# Project_2.net
KiCad netlist of a schematic drawn in EAGLE
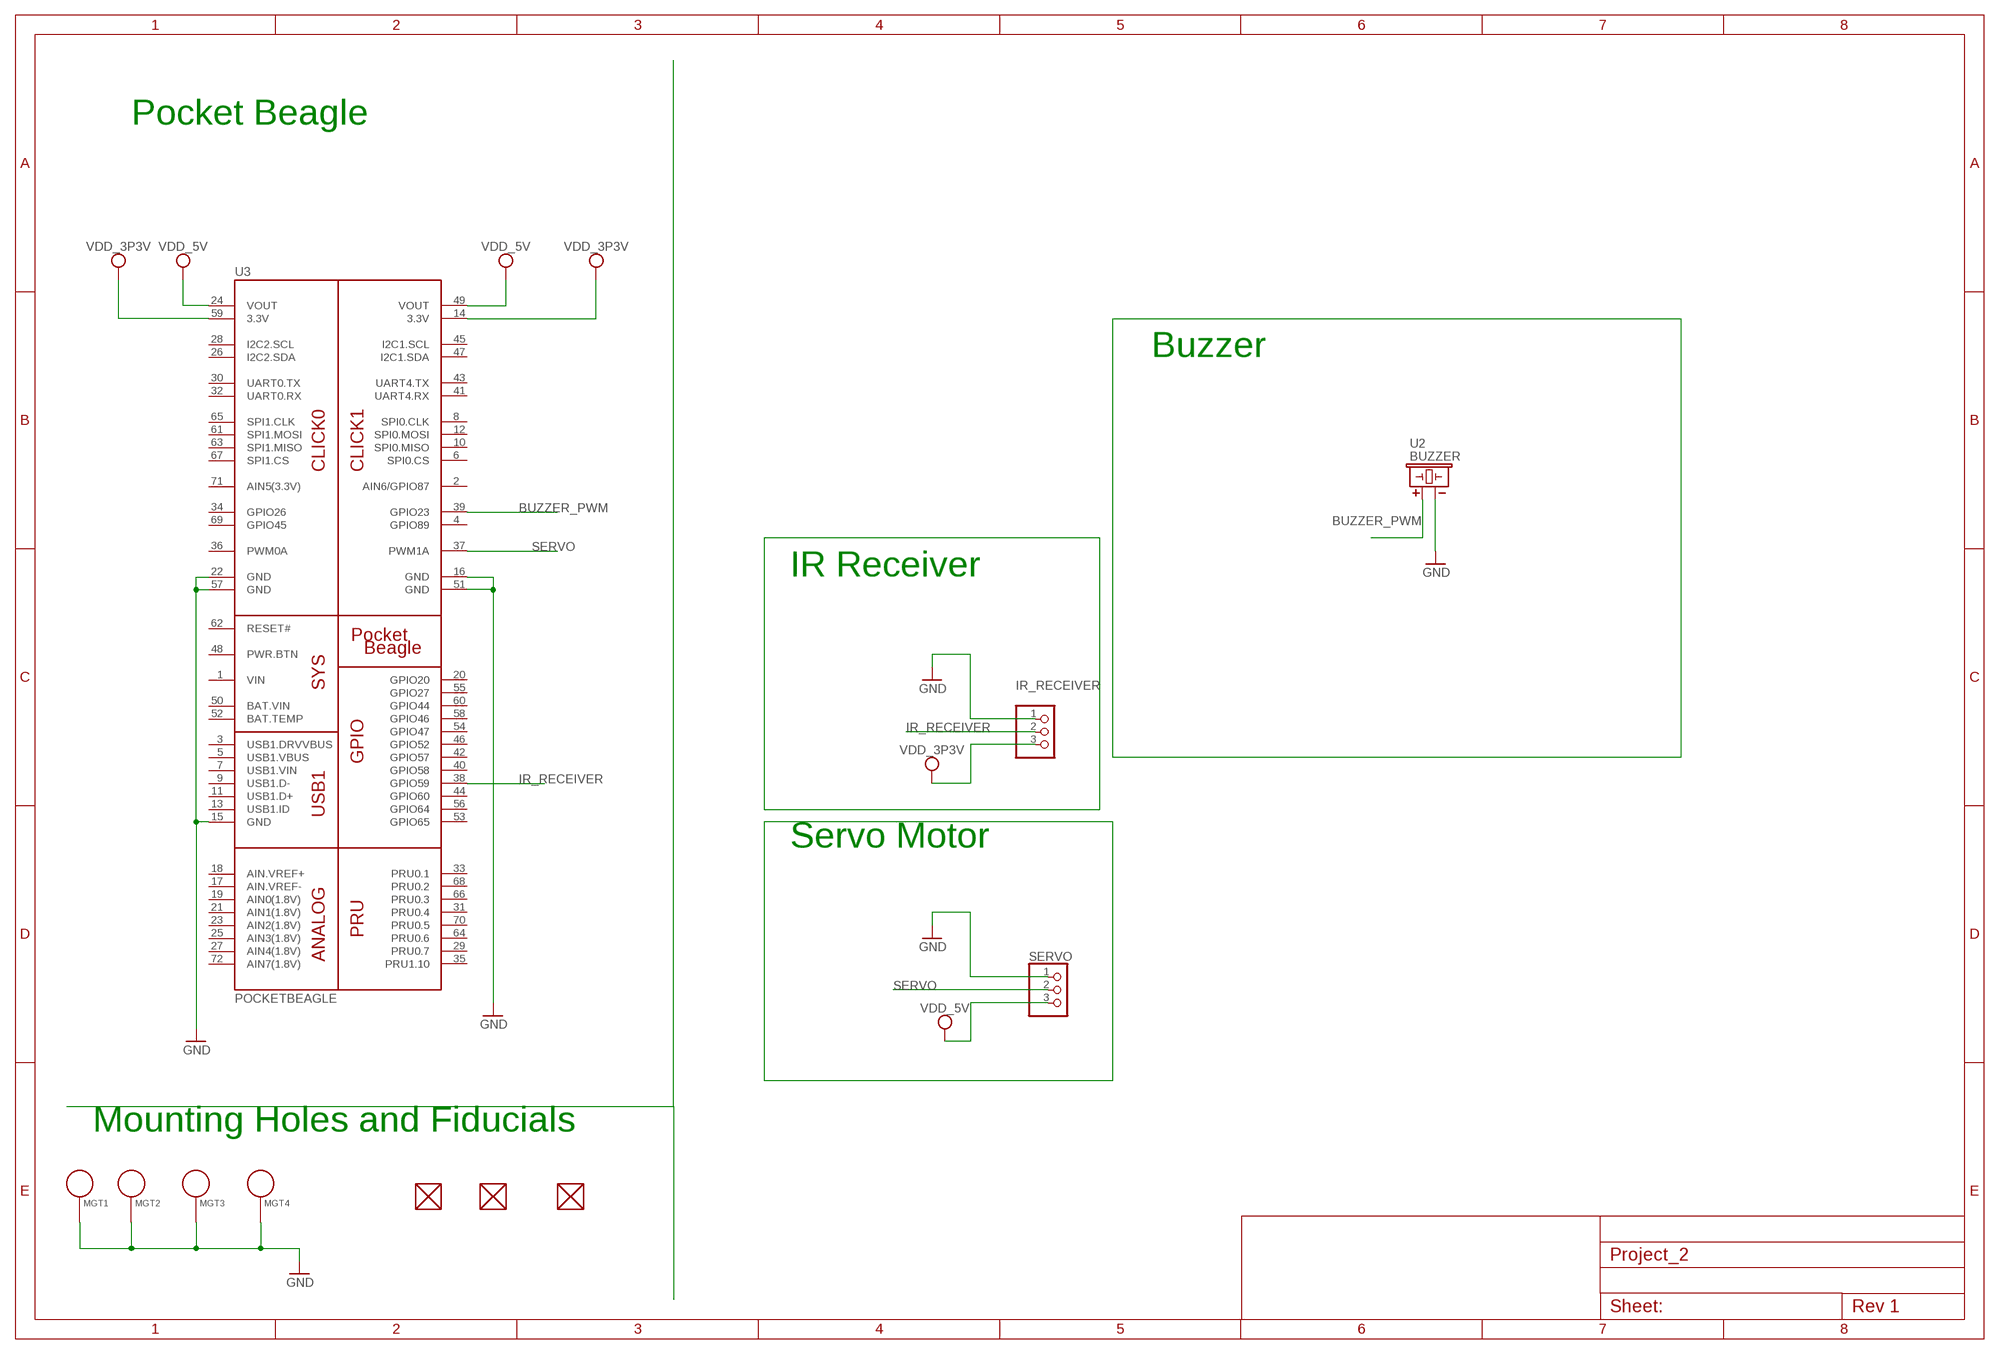
[diagram p0: schematic, sheet 1]

(export (version "E")
  (design (tool "Eeschema 10.0.6"))
  (components
    (comp (ref "FUD1")
      (value "FIDUCIAL")
      (footprint "eagle-import:FIDUCIAL_40MIL")
      (libsource (lib "eagle-import") (part "FIDUCIAL"))
    )
    (comp (ref "FUD2")
      (value "FIDUCIAL")
      (footprint "eagle-import:FIDUCIAL_40MIL")
      (libsource (lib "eagle-import") (part "FIDUCIAL"))
    )
    (comp (ref "FUD3")
      (value "FIDUCIAL")
      (footprint "eagle-import:FIDUCIAL_40MIL")
      (libsource (lib "eagle-import") (part "FIDUCIAL"))
    )
    (comp (ref "IR_RECEIVER")
      (value "PINHD-1X3")
      (footprint "eagle-import:1X03")
      (libsource (lib "eagle-import") (part "PINHD-1X3"))
    )
    (comp (ref "MGT1")
      (value "MOUNTING_HOLE")
      (footprint "eagle-import:MOUNTING_HOLE")
      (libsource (lib "eagle-import") (part "MOUNTING_HOLE"))
    )
    (comp (ref "MGT2")
      (value "MOUNTING_HOLE")
      (footprint "eagle-import:MOUNTING_HOLE")
      (libsource (lib "eagle-import") (part "MOUNTING_HOLE"))
    )
    (comp (ref "MGT3")
      (value "MOUNTING_HOLE")
      (footprint "eagle-import:MOUNTING_HOLE")
      (libsource (lib "eagle-import") (part "MOUNTING_HOLE"))
    )
    (comp (ref "MGT4")
      (value "MOUNTING_HOLE")
      (footprint "eagle-import:MOUNTING_HOLE")
      (libsource (lib "eagle-import") (part "MOUNTING_HOLE"))
    )
    (comp (ref "SERVO")
      (value "PINHD-1X3")
      (footprint "eagle-import:1X03")
      (libsource (lib "eagle-import") (part "PINHD-1X3"))
    )
    (comp (ref "U2")
      (value "BUZZER")
      (footprint "eagle-import:BUZZER_6.5MM")
      (libsource (lib "eagle-import") (part "BUZZER"))
    )
    (comp (ref "U3")
      (value "POCKETBEAGLE")
      (footprint "eagle-import:POCKETBEAGLE")
      (libsource (lib "eagle-import") (part "POCKETBEAGLE"))
    )
  )
  (nets
    (net (code "1") (name "/BAT.VIN") (class "Default")
      (node (ref "U3") (pin "50") (pinfunction "BAT.VIN_50") (pintype "power_in"))
    )
    (net (code "2") (name "/BUZZER_PWM") (class "Default")
      (node (ref "U2") (pin "+") (pinfunction "+_+") (pintype "passive"))
      (node (ref "U3") (pin "39") (pinfunction "GPIO23_39") (pintype "bidirectional"))
    )
    (net (code "3") (name "/IR_RECEIVER") (class "Default")
      (node (ref "IR_RECEIVER") (pin "2") (pinfunction "2_2") (pintype "passive"))
      (node (ref "U3") (pin "38") (pinfunction "GPIO59_38") (pintype "bidirectional"))
    )
    (net (code "4") (name "/SERVO") (class "Default")
      (node (ref "SERVO") (pin "2") (pinfunction "2_2") (pintype "passive"))
      (node (ref "U3") (pin "37") (pinfunction "PWM1A_37") (pintype "bidirectional"))
    )
    (net (code "5") (name "/VIN") (class "Default")
      (node (ref "U3") (pin "1") (pinfunction "VIN_1") (pintype "power_in"))
    )
    (net (code "6") (name "GND") (class "Default")
      (node (ref "IR_RECEIVER") (pin "1") (pinfunction "1_1") (pintype "passive"))
      (node (ref "MGT1") (pin "P$1") (pinfunction "P$1_P$1") (pintype "bidirectional"))
      (node (ref "MGT2") (pin "P$1") (pinfunction "P$1_P$1") (pintype "bidirectional"))
      (node (ref "MGT3") (pin "P$1") (pinfunction "P$1_P$1") (pintype "bidirectional"))
      (node (ref "MGT4") (pin "P$1") (pinfunction "P$1_P$1") (pintype "bidirectional"))
      (node (ref "SERVO") (pin "1") (pinfunction "1_1") (pintype "passive"))
      (node (ref "U2") (pin "-") (pinfunction "-_-") (pintype "passive"))
      (node (ref "U3") (pin "15") (pinfunction "GND_15") (pintype "bidirectional"))
      (node (ref "U3") (pin "16") (pinfunction "GND_16") (pintype "power_in"))
      (node (ref "U3") (pin "22") (pinfunction "GND_22") (pintype "power_in"))
      (node (ref "U3") (pin "51") (pinfunction "GND_51") (pintype "power_in"))
      (node (ref "U3") (pin "57") (pinfunction "GND_57") (pintype "power_in"))
    )
    (net (code "7") (name "VDD_3P3V") (class "Default")
      (node (ref "IR_RECEIVER") (pin "3") (pinfunction "3_3") (pintype "passive"))
      (node (ref "U3") (pin "14") (pinfunction "3.3V_14") (pintype "power_in"))
      (node (ref "U3") (pin "59") (pinfunction "3.3V_59") (pintype "power_in"))
    )
    (net (code "8") (name "VDD_5V") (class "Default")
      (node (ref "SERVO") (pin "3") (pinfunction "3_3") (pintype "passive"))
      (node (ref "U3") (pin "24") (pinfunction "VOUT_24") (pintype "power_in"))
      (node (ref "U3") (pin "49") (pinfunction "VOUT_49") (pintype "power_in"))
    )
    (net (code "9") (name "unconnected-(FUD1-PadP$1)") (class "Default")
      (node (ref "FUD1") (pin "P$1") (pinfunction "P$1_P$1") (pintype "no_connect"))
    )
    (net (code "10") (name "unconnected-(FUD2-PadP$1)") (class "Default")
      (node (ref "FUD2") (pin "P$1") (pinfunction "P$1_P$1") (pintype "no_connect"))
    )
    (net (code "11") (name "unconnected-(FUD3-PadP$1)") (class "Default")
      (node (ref "FUD3") (pin "P$1") (pinfunction "P$1_P$1") (pintype "no_connect"))
    )
    (net (code "12") (name "unconnected-(U3-AIN.VREF+-Pad18)") (class "Default")
      (node (ref "U3") (pin "18") (pinfunction "AIN.VREF+_18") (pintype "input"))
    )
    (net (code "13") (name "unconnected-(U3-AIN.VREF--Pad17)") (class "Default")
      (node (ref "U3") (pin "17") (pinfunction "AIN.VREF-_17") (pintype "input"))
    )
    (net (code "14") (name "unconnected-(U3-AIN0(1.8V)-Pad19)") (class "Default")
      (node (ref "U3") (pin "19") (pinfunction "AIN0(1.8V)_19") (pintype "input"))
    )
    (net (code "15") (name "unconnected-(U3-AIN1(1.8V)-Pad21)") (class "Default")
      (node (ref "U3") (pin "21") (pinfunction "AIN1(1.8V)_21") (pintype "input"))
    )
    (net (code "16") (name "unconnected-(U3-AIN2(1.8V)-Pad23)") (class "Default")
      (node (ref "U3") (pin "23") (pinfunction "AIN2(1.8V)_23") (pintype "input"))
    )
    (net (code "17") (name "unconnected-(U3-AIN3(1.8V)-Pad25)") (class "Default")
      (node (ref "U3") (pin "25") (pinfunction "AIN3(1.8V)_25") (pintype "input"))
    )
    (net (code "18") (name "unconnected-(U3-AIN4(1.8V)-Pad27)") (class "Default")
      (node (ref "U3") (pin "27") (pinfunction "AIN4(1.8V)_27") (pintype "input"))
    )
    (net (code "19") (name "unconnected-(U3-AIN5(3.3V)-Pad71)") (class "Default")
      (node (ref "U3") (pin "71") (pinfunction "AIN5(3.3V)_71") (pintype "bidirectional"))
    )
    (net (code "20") (name "unconnected-(U3-AIN6{slash}GPIO87-Pad2)") (class "Default")
      (node (ref "U3") (pin "2") (pinfunction "AIN6/GPIO87_2") (pintype "bidirectional"))
    )
    (net (code "21") (name "unconnected-(U3-AIN7(1.8V)-Pad72)") (class "Default")
      (node (ref "U3") (pin "72") (pinfunction "AIN7(1.8V)_72") (pintype "input"))
    )
    (net (code "22") (name "unconnected-(U3-BAT.TEMP-Pad52)") (class "Default")
      (node (ref "U3") (pin "52") (pinfunction "BAT.TEMP_52") (pintype "input"))
    )
    (net (code "23") (name "unconnected-(U3-GPIO20-Pad20)") (class "Default")
      (node (ref "U3") (pin "20") (pinfunction "GPIO20_20") (pintype "bidirectional"))
    )
    (net (code "24") (name "unconnected-(U3-GPIO26-Pad34)") (class "Default")
      (node (ref "U3") (pin "34") (pinfunction "GPIO26_34") (pintype "bidirectional"))
    )
    (net (code "25") (name "unconnected-(U3-GPIO27-Pad55)") (class "Default")
      (node (ref "U3") (pin "55") (pinfunction "GPIO27_55") (pintype "bidirectional"))
    )
    (net (code "26") (name "unconnected-(U3-GPIO44-Pad60)") (class "Default")
      (node (ref "U3") (pin "60") (pinfunction "GPIO44_60") (pintype "bidirectional"))
    )
    (net (code "27") (name "unconnected-(U3-GPIO45-Pad69)") (class "Default")
      (node (ref "U3") (pin "69") (pinfunction "GPIO45_69") (pintype "bidirectional"))
    )
    (net (code "28") (name "unconnected-(U3-GPIO46-Pad58)") (class "Default")
      (node (ref "U3") (pin "58") (pinfunction "GPIO46_58") (pintype "bidirectional"))
    )
    (net (code "29") (name "unconnected-(U3-GPIO47-Pad54)") (class "Default")
      (node (ref "U3") (pin "54") (pinfunction "GPIO47_54") (pintype "bidirectional"))
    )
    (net (code "30") (name "unconnected-(U3-GPIO52-Pad46)") (class "Default")
      (node (ref "U3") (pin "46") (pinfunction "GPIO52_46") (pintype "bidirectional"))
    )
    (net (code "31") (name "unconnected-(U3-GPIO57-Pad42)") (class "Default")
      (node (ref "U3") (pin "42") (pinfunction "GPIO57_42") (pintype "bidirectional"))
    )
    (net (code "32") (name "unconnected-(U3-GPIO58-Pad40)") (class "Default")
      (node (ref "U3") (pin "40") (pinfunction "GPIO58_40") (pintype "bidirectional"))
    )
    (net (code "33") (name "unconnected-(U3-GPIO60-Pad44)") (class "Default")
      (node (ref "U3") (pin "44") (pinfunction "GPIO60_44") (pintype "bidirectional"))
    )
    (net (code "34") (name "unconnected-(U3-GPIO64-Pad56)") (class "Default")
      (node (ref "U3") (pin "56") (pinfunction "GPIO64_56") (pintype "bidirectional"))
    )
    (net (code "35") (name "unconnected-(U3-GPIO65-Pad53)") (class "Default")
      (node (ref "U3") (pin "53") (pinfunction "GPIO65_53") (pintype "bidirectional"))
    )
    (net (code "36") (name "unconnected-(U3-GPIO89-Pad4)") (class "Default")
      (node (ref "U3") (pin "4") (pinfunction "GPIO89_4") (pintype "bidirectional"))
    )
    (net (code "37") (name "unconnected-(U3-I2C1.SCL-Pad45)") (class "Default")
      (node (ref "U3") (pin "45") (pinfunction "I2C1.SCL_45") (pintype "bidirectional"))
    )
    (net (code "38") (name "unconnected-(U3-I2C1.SDA-Pad47)") (class "Default")
      (node (ref "U3") (pin "47") (pinfunction "I2C1.SDA_47") (pintype "bidirectional"))
    )
    (net (code "39") (name "unconnected-(U3-I2C2.SCL-Pad28)") (class "Default")
      (node (ref "U3") (pin "28") (pinfunction "I2C2.SCL_28") (pintype "bidirectional"))
    )
    (net (code "40") (name "unconnected-(U3-I2C2.SDA-Pad26)") (class "Default")
      (node (ref "U3") (pin "26") (pinfunction "I2C2.SDA_26") (pintype "bidirectional"))
    )
    (net (code "41") (name "unconnected-(U3-PRU0.1-Pad33)") (class "Default")
      (node (ref "U3") (pin "33") (pinfunction "PRU0.1_33") (pintype "bidirectional"))
    )
    (net (code "42") (name "unconnected-(U3-PRU0.2-Pad68)") (class "Default")
      (node (ref "U3") (pin "68") (pinfunction "PRU0.2_68") (pintype "bidirectional"))
    )
    (net (code "43") (name "unconnected-(U3-PRU0.3-Pad66)") (class "Default")
      (node (ref "U3") (pin "66") (pinfunction "PRU0.3_66") (pintype "bidirectional"))
    )
    (net (code "44") (name "unconnected-(U3-PRU0.4-Pad31)") (class "Default")
      (node (ref "U3") (pin "31") (pinfunction "PRU0.4_31") (pintype "bidirectional"))
    )
    (net (code "45") (name "unconnected-(U3-PRU0.5-Pad70)") (class "Default")
      (node (ref "U3") (pin "70") (pinfunction "PRU0.5_70") (pintype "bidirectional"))
    )
    (net (code "46") (name "unconnected-(U3-PRU0.6-Pad64)") (class "Default")
      (node (ref "U3") (pin "64") (pinfunction "PRU0.6_64") (pintype "bidirectional"))
    )
    (net (code "47") (name "unconnected-(U3-PRU0.7-Pad29)") (class "Default")
      (node (ref "U3") (pin "29") (pinfunction "PRU0.7_29") (pintype "bidirectional"))
    )
    (net (code "48") (name "unconnected-(U3-PRU1.10-Pad35)") (class "Default")
      (node (ref "U3") (pin "35") (pinfunction "PRU1.10_35") (pintype "bidirectional"))
    )
    (net (code "49") (name "unconnected-(U3-PWM0A-Pad36)") (class "Default")
      (node (ref "U3") (pin "36") (pinfunction "PWM0A_36") (pintype "bidirectional"))
    )
    (net (code "50") (name "unconnected-(U3-PWR.BTN-Pad48)") (class "Default")
      (node (ref "U3") (pin "48") (pinfunction "PWR.BTN_48") (pintype "input"))
    )
    (net (code "51") (name "unconnected-(U3-RESET#-Pad62)") (class "Default")
      (node (ref "U3") (pin "62") (pinfunction "RESET#_62") (pintype "input"))
    )
    (net (code "52") (name "unconnected-(U3-SPI0.CLK-Pad8)") (class "Default")
      (node (ref "U3") (pin "8") (pinfunction "SPI0.CLK_8") (pintype "bidirectional"))
    )
    (net (code "53") (name "unconnected-(U3-SPI0.CS-Pad6)") (class "Default")
      (node (ref "U3") (pin "6") (pinfunction "SPI0.CS_6") (pintype "bidirectional"))
    )
    (net (code "54") (name "unconnected-(U3-SPI0.MISO-Pad10)") (class "Default")
      (node (ref "U3") (pin "10") (pinfunction "SPI0.MISO_10") (pintype "bidirectional"))
    )
    (net (code "55") (name "unconnected-(U3-SPI0.MOSI-Pad12)") (class "Default")
      (node (ref "U3") (pin "12") (pinfunction "SPI0.MOSI_12") (pintype "bidirectional"))
    )
    (net (code "56") (name "unconnected-(U3-SPI1.CLK-Pad65)") (class "Default")
      (node (ref "U3") (pin "65") (pinfunction "SPI1.CLK_65") (pintype "bidirectional"))
    )
    (net (code "57") (name "unconnected-(U3-SPI1.CS-Pad67)") (class "Default")
      (node (ref "U3") (pin "67") (pinfunction "SPI1.CS_67") (pintype "bidirectional"))
    )
    (net (code "58") (name "unconnected-(U3-SPI1.MISO-Pad63)") (class "Default")
      (node (ref "U3") (pin "63") (pinfunction "SPI1.MISO_63") (pintype "bidirectional"))
    )
    (net (code "59") (name "unconnected-(U3-SPI1.MOSI-Pad61)") (class "Default")
      (node (ref "U3") (pin "61") (pinfunction "SPI1.MOSI_61") (pintype "bidirectional"))
    )
    (net (code "60") (name "unconnected-(U3-UART0.RX-Pad32)") (class "Default")
      (node (ref "U3") (pin "32") (pinfunction "UART0.RX_32") (pintype "bidirectional"))
    )
    (net (code "61") (name "unconnected-(U3-UART0.TX-Pad30)") (class "Default")
      (node (ref "U3") (pin "30") (pinfunction "UART0.TX_30") (pintype "bidirectional"))
    )
    (net (code "62") (name "unconnected-(U3-UART4.RX-Pad41)") (class "Default")
      (node (ref "U3") (pin "41") (pinfunction "UART4.RX_41") (pintype "bidirectional"))
    )
    (net (code "63") (name "unconnected-(U3-UART4.TX-Pad43)") (class "Default")
      (node (ref "U3") (pin "43") (pinfunction "UART4.TX_43") (pintype "bidirectional"))
    )
    (net (code "64") (name "unconnected-(U3-USB1.D+-Pad11)") (class "Default")
      (node (ref "U3") (pin "11") (pinfunction "USB1.D+_11") (pintype "bidirectional"))
    )
    (net (code "65") (name "unconnected-(U3-USB1.D--Pad9)") (class "Default")
      (node (ref "U3") (pin "9") (pinfunction "USB1.D-_9") (pintype "bidirectional"))
    )
    (net (code "66") (name "unconnected-(U3-USB1.DRVVBUS-Pad3)") (class "Default")
      (node (ref "U3") (pin "3") (pinfunction "USB1.DRVVBUS_3") (pintype "bidirectional"))
    )
    (net (code "67") (name "unconnected-(U3-USB1.ID-Pad13)") (class "Default")
      (node (ref "U3") (pin "13") (pinfunction "USB1.ID_13") (pintype "bidirectional"))
    )
    (net (code "68") (name "unconnected-(U3-USB1.VBUS-Pad5)") (class "Default")
      (node (ref "U3") (pin "5") (pinfunction "USB1.VBUS_5") (pintype "bidirectional"))
    )
    (net (code "69") (name "unconnected-(U3-USB1.VIN-Pad7)") (class "Default")
      (node (ref "U3") (pin "7") (pinfunction "USB1.VIN_7") (pintype "bidirectional"))
    )
  )
)
